# speedy_barebone.net
KiCad netlist of a schematic drawn in EAGLE
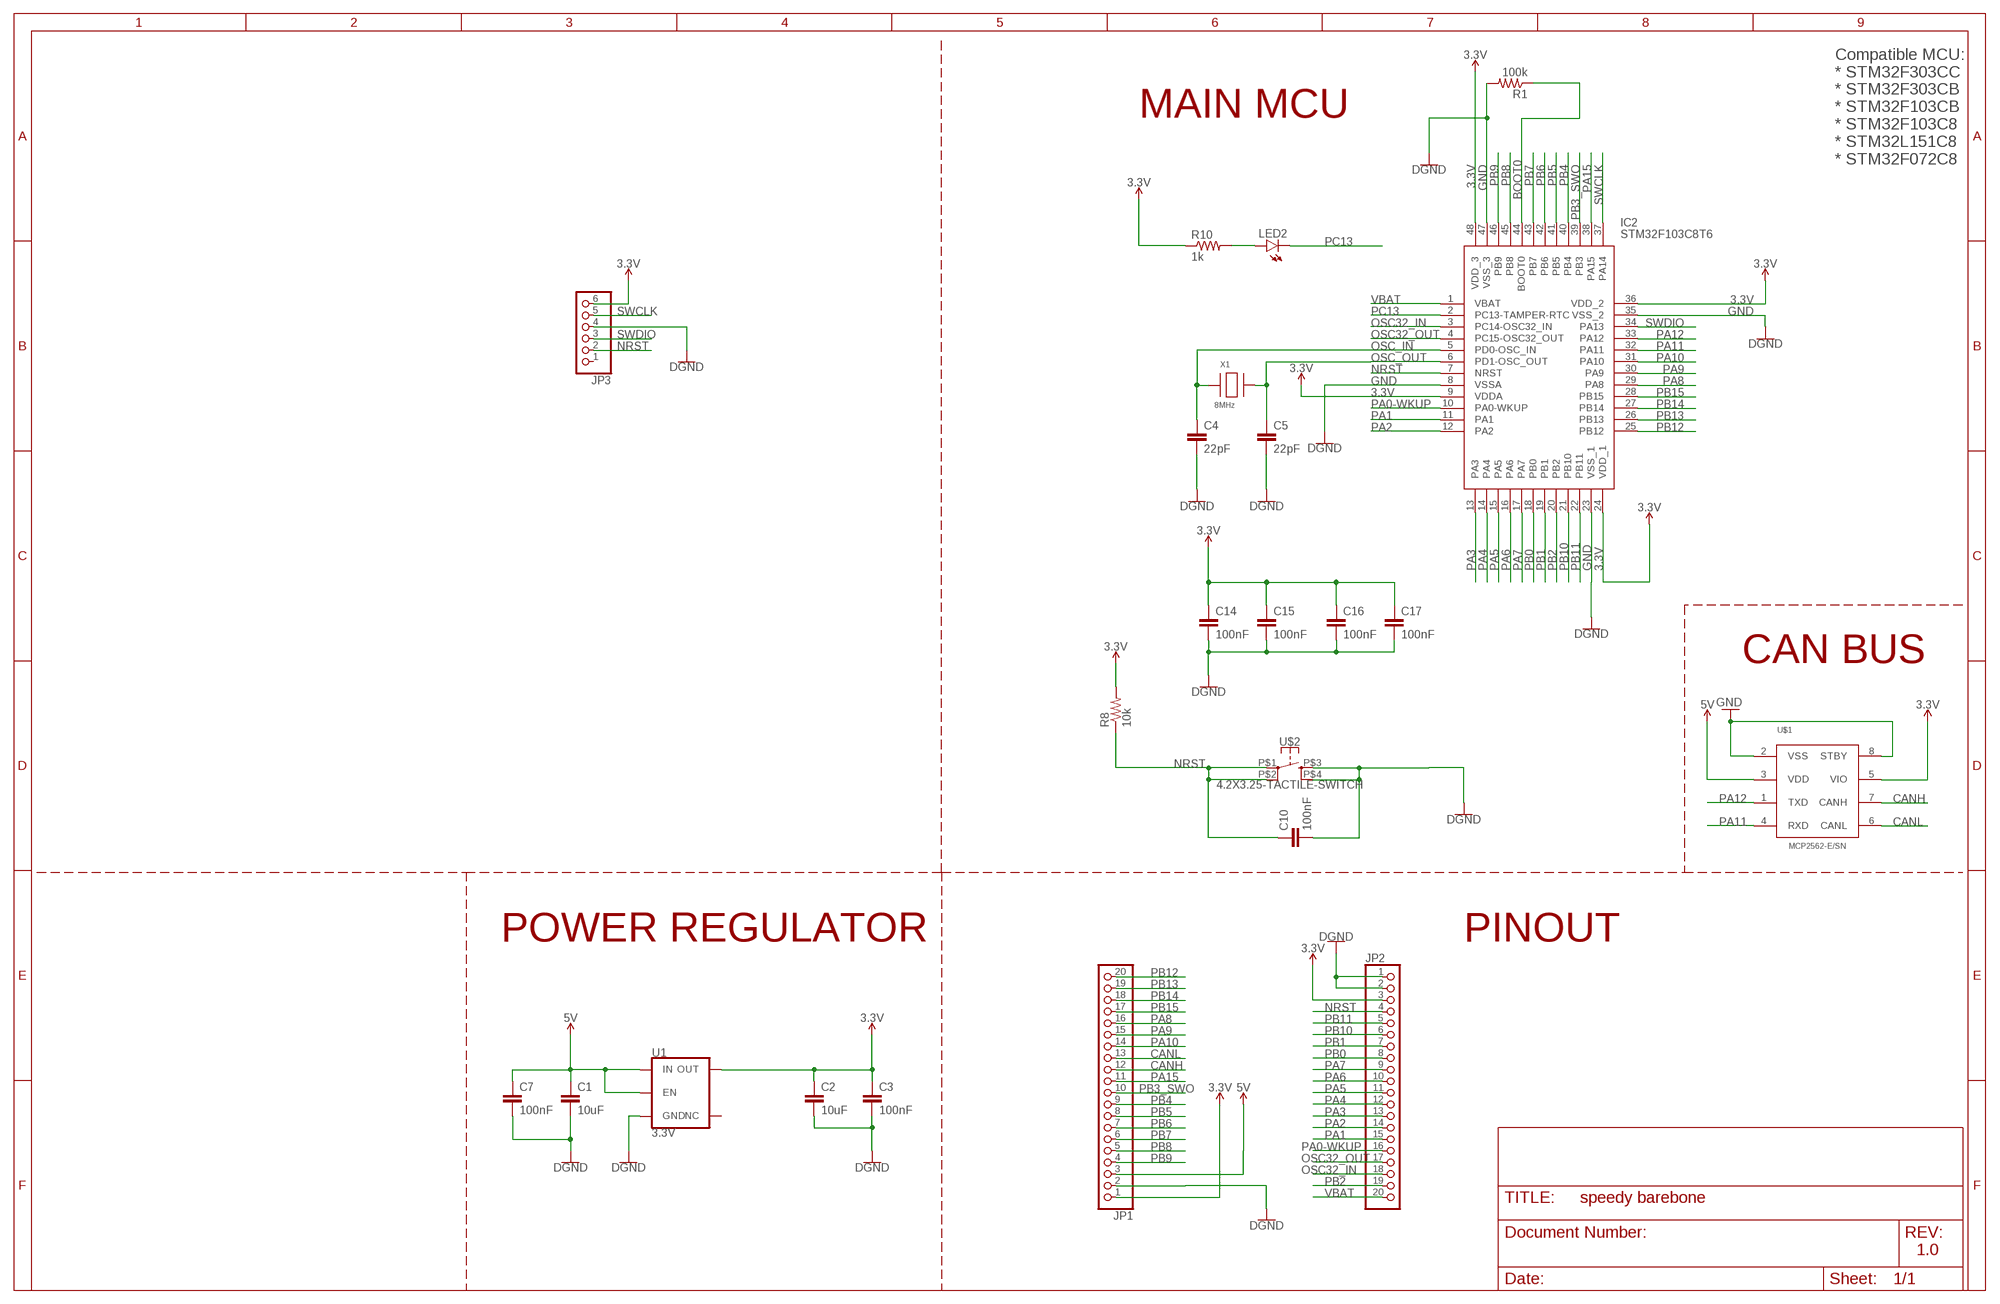
[diagram p0: schematic, sheet 1]

(export (version "E")
  (design (tool "Eeschema 10.0.6"))
  (components
    (comp (ref "C1")
      (value "10uF")
      (footprint "eagle-import:C0805")
      (libsource (lib "eagle-import") (part "C-EUC0805"))
    )
    (comp (ref "C2")
      (value "10uF")
      (footprint "eagle-import:C0805")
      (libsource (lib "eagle-import") (part "C-EUC0805"))
    )
    (comp (ref "C3")
      (value "100nF")
      (footprint "eagle-import:C0603")
      (libsource (lib "eagle-import") (part "C-EUC0603"))
    )
    (comp (ref "C4")
      (value "22pF")
      (footprint "eagle-import:C0603")
      (libsource (lib "eagle-import") (part "resistor_348_C-EUC0603"))
    )
    (comp (ref "C5")
      (value "22pF")
      (footprint "eagle-import:C0603")
      (libsource (lib "eagle-import") (part "resistor_348_C-EUC0603"))
    )
    (comp (ref "C7")
      (value "100nF")
      (footprint "eagle-import:C0603")
      (libsource (lib "eagle-import") (part "C-EUC0603"))
    )
    (comp (ref "C10")
      (value "100nF")
      (footprint "eagle-import:C0603")
      (libsource (lib "eagle-import") (part "C-EUC0603"))
    )
    (comp (ref "C14")
      (value "100nF")
      (footprint "eagle-import:C0603")
      (libsource (lib "eagle-import") (part "C-EUC0603"))
    )
    (comp (ref "C15")
      (value "100nF")
      (footprint "eagle-import:C0603")
      (libsource (lib "eagle-import") (part "C-EUC0603"))
    )
    (comp (ref "C16")
      (value "100nF")
      (footprint "eagle-import:C0603")
      (libsource (lib "eagle-import") (part "C-EUC0603"))
    )
    (comp (ref "C17")
      (value "100nF")
      (footprint "eagle-import:C0603")
      (libsource (lib "eagle-import") (part "C-EUC0603"))
    )
    (comp (ref "IC2")
      (value "STM32F103C8T6")
      (footprint "eagle-import:QFP50P900X900X160-48N")
      (fields (field (name "MOUSER_PART_NUMBER") "511-STM32F103C8T6"))
      (libsource (lib "eagle-import") (part "STM32F103C8T6"))
    )
    (comp (ref "JP1")
      (value "PINHD-1X20")
      (footprint "eagle-import:1X20")
      (libsource (lib "eagle-import") (part "PINHD-1X20"))
    )
    (comp (ref "JP2")
      (value "PINHD-1X20")
      (footprint "eagle-import:1X20")
      (libsource (lib "eagle-import") (part "PINHD-1X20"))
    )
    (comp (ref "JP3")
      (value "PINHD-1X6")
      (footprint "eagle-import:1X06")
      (libsource (lib "eagle-import") (part "PINHD-1X6"))
    )
    (comp (ref "LED2")
      (value "LEDCHIP-LED0805")
      (footprint "eagle-import:CHIP-LED0805")
      (libsource (lib "eagle-import") (part "LEDCHIP-LED0805"))
    )
    (comp (ref "R1")
      (value "100k")
      (footprint "eagle-import:R0603")
      (libsource (lib "eagle-import") (part "R-US_R0603"))
    )
    (comp (ref "R8")
      (value "10k")
      (footprint "eagle-import:R0603")
      (libsource (lib "eagle-import") (part "R-US_R0603"))
    )
    (comp (ref "R10")
      (value "1k")
      (footprint "eagle-import:R0603")
      (libsource (lib "eagle-import") (part "R-US_R0603"))
    )
    (comp (ref "U$1")
      (value "MCP2562-E/SN")
      (footprint "eagle-import:SOIC8")
      (libsource (lib "eagle-import") (part "MCP2562-E/SN"))
    )
    (comp (ref "U$2")
      (value "4.2X3.25-TACTILE-SWITCH")
      (footprint "eagle-import:4.2X3.25")
      (libsource (lib "eagle-import") (part "4.2X3.25-TACTILE-SWITCH"))
    )
    (comp (ref "U1")
      (value "3.3V")
      (footprint "eagle-import:SOT23-5")
      (libsource (lib "eagle-import") (part "V_REG_AP2112K-3.3V"))
    )
    (comp (ref "X1")
      (value "8MHz")
      (footprint "eagle-import:NX5032")
      (libsource (lib "eagle-import") (part "XTALNX5032"))
    )
  )
  (nets
    (net (code "1") (name "/BOOT0") (class "Default")
      (node (ref "IC2") (pin "44") (pinfunction "BOOT0_44") (pintype "bidirectional"))
      (node (ref "R1") (pin "1") (pinfunction "1_1") (pintype "passive"))
    )
    (net (code "2") (name "/CANH") (class "Default")
      (node (ref "JP1") (pin "12") (pinfunction "12_12") (pintype "passive"))
      (node (ref "U$1") (pin "7") (pinfunction "CANH_7") (pintype "bidirectional"))
    )
    (net (code "3") (name "/CANL") (class "Default")
      (node (ref "JP1") (pin "13") (pinfunction "13_13") (pintype "passive"))
      (node (ref "U$1") (pin "6") (pinfunction "CANL_6") (pintype "bidirectional"))
    )
    (net (code "4") (name "/NRST") (class "Default")
      (node (ref "C10") (pin "1") (pinfunction "1_1") (pintype "passive"))
      (node (ref "IC2") (pin "7") (pinfunction "NRST_7") (pintype "input"))
      (node (ref "JP2") (pin "4") (pinfunction "4_4") (pintype "passive"))
      (node (ref "JP3") (pin "2") (pinfunction "2_2") (pintype "passive"))
      (node (ref "R8") (pin "1") (pinfunction "1_1") (pintype "passive"))
      (node (ref "U$2") (pin "P$1") (pinfunction "1_P$1") (pintype "passive"))
      (node (ref "U$2") (pin "P$2") (pinfunction "2_P$2") (pintype "passive"))
    )
    (net (code "5") (name "/OSC32_IN") (class "Default")
      (node (ref "IC2") (pin "3") (pinfunction "PC14-OSC32_IN_3") (pintype "input"))
      (node (ref "JP2") (pin "18") (pinfunction "18_18") (pintype "passive"))
    )
    (net (code "6") (name "/OSC32_OUT") (class "Default")
      (node (ref "IC2") (pin "4") (pinfunction "PC15-OSC32_OUT_4") (pintype "output"))
      (node (ref "JP2") (pin "17") (pinfunction "17_17") (pintype "passive"))
    )
    (net (code "7") (name "/OSC_IN") (class "Default")
      (node (ref "C4") (pin "1") (pinfunction "1_1") (pintype "passive"))
      (node (ref "IC2") (pin "5") (pinfunction "PD0-OSC_IN_5") (pintype "input"))
      (node (ref "X1") (pin "P$1") (pinfunction "P$1_P$1") (pintype "bidirectional"))
    )
    (net (code "8") (name "/OSC_OUT") (class "Default")
      (node (ref "C5") (pin "1") (pinfunction "1_1") (pintype "passive"))
      (node (ref "IC2") (pin "6") (pinfunction "PD1-OSC_OUT_6") (pintype "output"))
      (node (ref "X1") (pin "P$2") (pinfunction "P$2_P$2") (pintype "bidirectional"))
    )
    (net (code "9") (name "/PA0-WKUP") (class "Default")
      (node (ref "IC2") (pin "10") (pinfunction "PA0-WKUP_10") (pintype "bidirectional"))
      (node (ref "JP2") (pin "16") (pinfunction "16_16") (pintype "passive"))
    )
    (net (code "10") (name "/PA1") (class "Default")
      (node (ref "IC2") (pin "11") (pinfunction "PA1_11") (pintype "bidirectional"))
      (node (ref "JP2") (pin "15") (pinfunction "15_15") (pintype "passive"))
    )
    (net (code "11") (name "/PA2") (class "Default")
      (node (ref "IC2") (pin "12") (pinfunction "PA2_12") (pintype "bidirectional"))
      (node (ref "JP2") (pin "14") (pinfunction "14_14") (pintype "passive"))
    )
    (net (code "12") (name "/PA3") (class "Default")
      (node (ref "IC2") (pin "13") (pinfunction "PA3_13") (pintype "bidirectional"))
      (node (ref "JP2") (pin "13") (pinfunction "13_13") (pintype "passive"))
    )
    (net (code "13") (name "/PA4") (class "Default")
      (node (ref "IC2") (pin "14") (pinfunction "PA4_14") (pintype "bidirectional"))
      (node (ref "JP2") (pin "12") (pinfunction "12_12") (pintype "passive"))
    )
    (net (code "14") (name "/PA5") (class "Default")
      (node (ref "IC2") (pin "15") (pinfunction "PA5_15") (pintype "bidirectional"))
      (node (ref "JP2") (pin "11") (pinfunction "11_11") (pintype "passive"))
    )
    (net (code "15") (name "/PA6") (class "Default")
      (node (ref "IC2") (pin "16") (pinfunction "PA6_16") (pintype "bidirectional"))
      (node (ref "JP2") (pin "10") (pinfunction "10_10") (pintype "passive"))
    )
    (net (code "16") (name "/PA7") (class "Default")
      (node (ref "IC2") (pin "17") (pinfunction "PA7_17") (pintype "bidirectional"))
      (node (ref "JP2") (pin "9") (pinfunction "9_9") (pintype "passive"))
    )
    (net (code "17") (name "/PA8") (class "Default")
      (node (ref "IC2") (pin "29") (pinfunction "PA8_29") (pintype "bidirectional"))
      (node (ref "JP1") (pin "16") (pinfunction "16_16") (pintype "passive"))
    )
    (net (code "18") (name "/PA9") (class "Default")
      (node (ref "IC2") (pin "30") (pinfunction "PA9_30") (pintype "bidirectional"))
      (node (ref "JP1") (pin "15") (pinfunction "15_15") (pintype "passive"))
    )
    (net (code "19") (name "/PA10") (class "Default")
      (node (ref "IC2") (pin "31") (pinfunction "PA10_31") (pintype "bidirectional"))
      (node (ref "JP1") (pin "14") (pinfunction "14_14") (pintype "passive"))
    )
    (net (code "20") (name "/PA11") (class "Default")
      (node (ref "IC2") (pin "32") (pinfunction "PA11_32") (pintype "bidirectional"))
      (node (ref "U$1") (pin "4") (pinfunction "RXD_4") (pintype "bidirectional"))
    )
    (net (code "21") (name "/PA12") (class "Default")
      (node (ref "IC2") (pin "33") (pinfunction "PA12_33") (pintype "bidirectional"))
      (node (ref "U$1") (pin "1") (pinfunction "TXD_1") (pintype "bidirectional"))
    )
    (net (code "22") (name "/PA15") (class "Default")
      (node (ref "IC2") (pin "38") (pinfunction "PA15_38") (pintype "bidirectional"))
      (node (ref "JP1") (pin "11") (pinfunction "11_11") (pintype "passive"))
    )
    (net (code "23") (name "/PB0") (class "Default")
      (node (ref "IC2") (pin "18") (pinfunction "PB0_18") (pintype "bidirectional"))
      (node (ref "JP2") (pin "8") (pinfunction "8_8") (pintype "passive"))
    )
    (net (code "24") (name "/PB1") (class "Default")
      (node (ref "IC2") (pin "19") (pinfunction "PB1_19") (pintype "bidirectional"))
      (node (ref "JP2") (pin "7") (pinfunction "7_7") (pintype "passive"))
    )
    (net (code "25") (name "/PB2") (class "Default")
      (node (ref "IC2") (pin "20") (pinfunction "PB2_20") (pintype "bidirectional"))
      (node (ref "JP2") (pin "19") (pinfunction "19_19") (pintype "passive"))
    )
    (net (code "26") (name "/PB3_SWO") (class "Default")
      (node (ref "IC2") (pin "39") (pinfunction "PB3_39") (pintype "bidirectional"))
      (node (ref "JP1") (pin "10") (pinfunction "10_10") (pintype "passive"))
    )
    (net (code "27") (name "/PB4") (class "Default")
      (node (ref "IC2") (pin "40") (pinfunction "PB4_40") (pintype "bidirectional"))
      (node (ref "JP1") (pin "9") (pinfunction "9_9") (pintype "passive"))
    )
    (net (code "28") (name "/PB5") (class "Default")
      (node (ref "IC2") (pin "41") (pinfunction "PB5_41") (pintype "bidirectional"))
      (node (ref "JP1") (pin "8") (pinfunction "8_8") (pintype "passive"))
    )
    (net (code "29") (name "/PB6") (class "Default")
      (node (ref "IC2") (pin "42") (pinfunction "PB6_42") (pintype "bidirectional"))
      (node (ref "JP1") (pin "7") (pinfunction "7_7") (pintype "passive"))
    )
    (net (code "30") (name "/PB7") (class "Default")
      (node (ref "IC2") (pin "43") (pinfunction "PB7_43") (pintype "bidirectional"))
      (node (ref "JP1") (pin "6") (pinfunction "6_6") (pintype "passive"))
    )
    (net (code "31") (name "/PB8") (class "Default")
      (node (ref "IC2") (pin "45") (pinfunction "PB8_45") (pintype "bidirectional"))
      (node (ref "JP1") (pin "5") (pinfunction "5_5") (pintype "passive"))
    )
    (net (code "32") (name "/PB9") (class "Default")
      (node (ref "IC2") (pin "46") (pinfunction "PB9_46") (pintype "bidirectional"))
      (node (ref "JP1") (pin "4") (pinfunction "4_4") (pintype "passive"))
    )
    (net (code "33") (name "/PB10") (class "Default")
      (node (ref "IC2") (pin "21") (pinfunction "PB10_21") (pintype "bidirectional"))
      (node (ref "JP2") (pin "6") (pinfunction "6_6") (pintype "passive"))
    )
    (net (code "34") (name "/PB11") (class "Default")
      (node (ref "IC2") (pin "22") (pinfunction "PB11_22") (pintype "bidirectional"))
      (node (ref "JP2") (pin "5") (pinfunction "5_5") (pintype "passive"))
    )
    (net (code "35") (name "/PB12") (class "Default")
      (node (ref "IC2") (pin "25") (pinfunction "PB12_25") (pintype "bidirectional"))
      (node (ref "JP1") (pin "20") (pinfunction "20_20") (pintype "passive"))
    )
    (net (code "36") (name "/PB13") (class "Default")
      (node (ref "IC2") (pin "26") (pinfunction "PB13_26") (pintype "bidirectional"))
      (node (ref "JP1") (pin "19") (pinfunction "19_19") (pintype "passive"))
    )
    (net (code "37") (name "/PB14") (class "Default")
      (node (ref "IC2") (pin "27") (pinfunction "PB14_27") (pintype "bidirectional"))
      (node (ref "JP1") (pin "18") (pinfunction "18_18") (pintype "passive"))
    )
    (net (code "38") (name "/PB15") (class "Default")
      (node (ref "IC2") (pin "28") (pinfunction "PB15_28") (pintype "bidirectional"))
      (node (ref "JP1") (pin "17") (pinfunction "17_17") (pintype "passive"))
    )
    (net (code "39") (name "/PC13") (class "Default")
      (node (ref "IC2") (pin "2") (pinfunction "PC13-TAMPER-RTC_2") (pintype "bidirectional"))
      (node (ref "LED2") (pin "C") (pinfunction "C_C") (pintype "passive"))
    )
    (net (code "40") (name "/SWCLK") (class "Default")
      (node (ref "IC2") (pin "37") (pinfunction "PA14_37") (pintype "bidirectional"))
      (node (ref "JP3") (pin "5") (pinfunction "5_5") (pintype "passive"))
    )
    (net (code "41") (name "/SWDIO") (class "Default")
      (node (ref "IC2") (pin "34") (pinfunction "PA13_34") (pintype "bidirectional"))
      (node (ref "JP3") (pin "3") (pinfunction "3_3") (pintype "passive"))
    )
    (net (code "42") (name "/VBAT") (class "Default")
      (node (ref "IC2") (pin "1") (pinfunction "VBAT_1") (pintype "bidirectional"))
      (node (ref "JP2") (pin "20") (pinfunction "20_20") (pintype "passive"))
    )
    (net (code "43") (name "3.3V") (class "Default")
      (node (ref "C14") (pin "1") (pinfunction "1_1") (pintype "passive"))
      (node (ref "C15") (pin "1") (pinfunction "1_1") (pintype "passive"))
      (node (ref "C16") (pin "1") (pinfunction "1_1") (pintype "passive"))
      (node (ref "C17") (pin "1") (pinfunction "1_1") (pintype "passive"))
      (node (ref "C2") (pin "1") (pinfunction "1_1") (pintype "passive"))
      (node (ref "C3") (pin "1") (pinfunction "1_1") (pintype "passive"))
      (node (ref "IC2") (pin "24") (pinfunction "VDD_1_24") (pintype "power_in"))
      (node (ref "IC2") (pin "36") (pinfunction "VDD_2_36") (pintype "power_in"))
      (node (ref "IC2") (pin "48") (pinfunction "VDD_3_48") (pintype "power_in"))
      (node (ref "IC2") (pin "9") (pinfunction "VDDA_9") (pintype "power_in"))
      (node (ref "JP1") (pin "1") (pinfunction "1_1") (pintype "passive"))
      (node (ref "JP2") (pin "3") (pinfunction "3_3") (pintype "passive"))
      (node (ref "JP3") (pin "6") (pinfunction "6_6") (pintype "passive"))
      (node (ref "R10") (pin "1") (pinfunction "1_1") (pintype "passive"))
      (node (ref "R8") (pin "2") (pinfunction "2_2") (pintype "passive"))
      (node (ref "U$1") (pin "5") (pinfunction "VIO_5") (pintype "bidirectional"))
      (node (ref "U1") (pin "5") (pinfunction "OUT_5") (pintype "passive"))
    )
    (net (code "44") (name "5V") (class "Default")
      (node (ref "C1") (pin "1") (pinfunction "1_1") (pintype "passive"))
      (node (ref "C7") (pin "1") (pinfunction "1_1") (pintype "passive"))
      (node (ref "JP1") (pin "3") (pinfunction "3_3") (pintype "passive"))
      (node (ref "U$1") (pin "3") (pinfunction "VDD_3") (pintype "bidirectional"))
      (node (ref "U1") (pin "1") (pinfunction "IN_1") (pintype "input"))
      (node (ref "U1") (pin "3") (pinfunction "EN_3") (pintype "input"))
    )
    (net (code "45") (name "DGND") (class "Default")
      (node (ref "C1") (pin "2") (pinfunction "2_2") (pintype "passive"))
      (node (ref "C10") (pin "2") (pinfunction "2_2") (pintype "passive"))
      (node (ref "C14") (pin "2") (pinfunction "2_2") (pintype "passive"))
      (node (ref "C15") (pin "2") (pinfunction "2_2") (pintype "passive"))
      (node (ref "C16") (pin "2") (pinfunction "2_2") (pintype "passive"))
      (node (ref "C17") (pin "2") (pinfunction "2_2") (pintype "passive"))
      (node (ref "C2") (pin "2") (pinfunction "2_2") (pintype "passive"))
      (node (ref "C3") (pin "2") (pinfunction "2_2") (pintype "passive"))
      (node (ref "C4") (pin "2") (pinfunction "2_2") (pintype "passive"))
      (node (ref "C5") (pin "2") (pinfunction "2_2") (pintype "passive"))
      (node (ref "C7") (pin "2") (pinfunction "2_2") (pintype "passive"))
      (node (ref "IC2") (pin "23") (pinfunction "VSS_1_23") (pintype "power_in"))
      (node (ref "IC2") (pin "35") (pinfunction "VSS_2_35") (pintype "power_in"))
      (node (ref "IC2") (pin "47") (pinfunction "VSS_3_47") (pintype "power_in"))
      (node (ref "IC2") (pin "8") (pinfunction "VSSA_8") (pintype "power_in"))
      (node (ref "JP1") (pin "2") (pinfunction "2_2") (pintype "passive"))
      (node (ref "JP2") (pin "1") (pinfunction "1_1") (pintype "passive"))
      (node (ref "JP2") (pin "2") (pinfunction "2_2") (pintype "passive"))
      (node (ref "JP3") (pin "4") (pinfunction "4_4") (pintype "passive"))
      (node (ref "R1") (pin "2") (pinfunction "2_2") (pintype "passive"))
      (node (ref "U$1") (pin "2") (pinfunction "VSS_2") (pintype "bidirectional"))
      (node (ref "U$1") (pin "8") (pinfunction "STBY_8") (pintype "bidirectional"))
      (node (ref "U$2") (pin "P$3") (pinfunction "3_P$3") (pintype "passive"))
      (node (ref "U$2") (pin "P$4") (pinfunction "4_P$4") (pintype "passive"))
      (node (ref "U1") (pin "2") (pinfunction "GND_2") (pintype "input"))
    )
    (net (code "46") (name "Net-(LED2-PadA)") (class "Default")
      (node (ref "LED2") (pin "A") (pinfunction "A_A") (pintype "passive"))
      (node (ref "R10") (pin "2") (pinfunction "2_2") (pintype "passive"))
    )
    (net (code "47") (name "unconnected-(JP3-Pad1)") (class "Default")
      (node (ref "JP3") (pin "1") (pinfunction "1_1") (pintype "passive"))
    )
    (net (code "48") (name "unconnected-(U1-NC-Pad4)") (class "Default")
      (node (ref "U1") (pin "4") (pinfunction "NC_4") (pintype "no_connect"))
    )
  )
)
